# ITG3200_Gyroscope.net
KiCad netlist of a schematic drawn in EAGLE
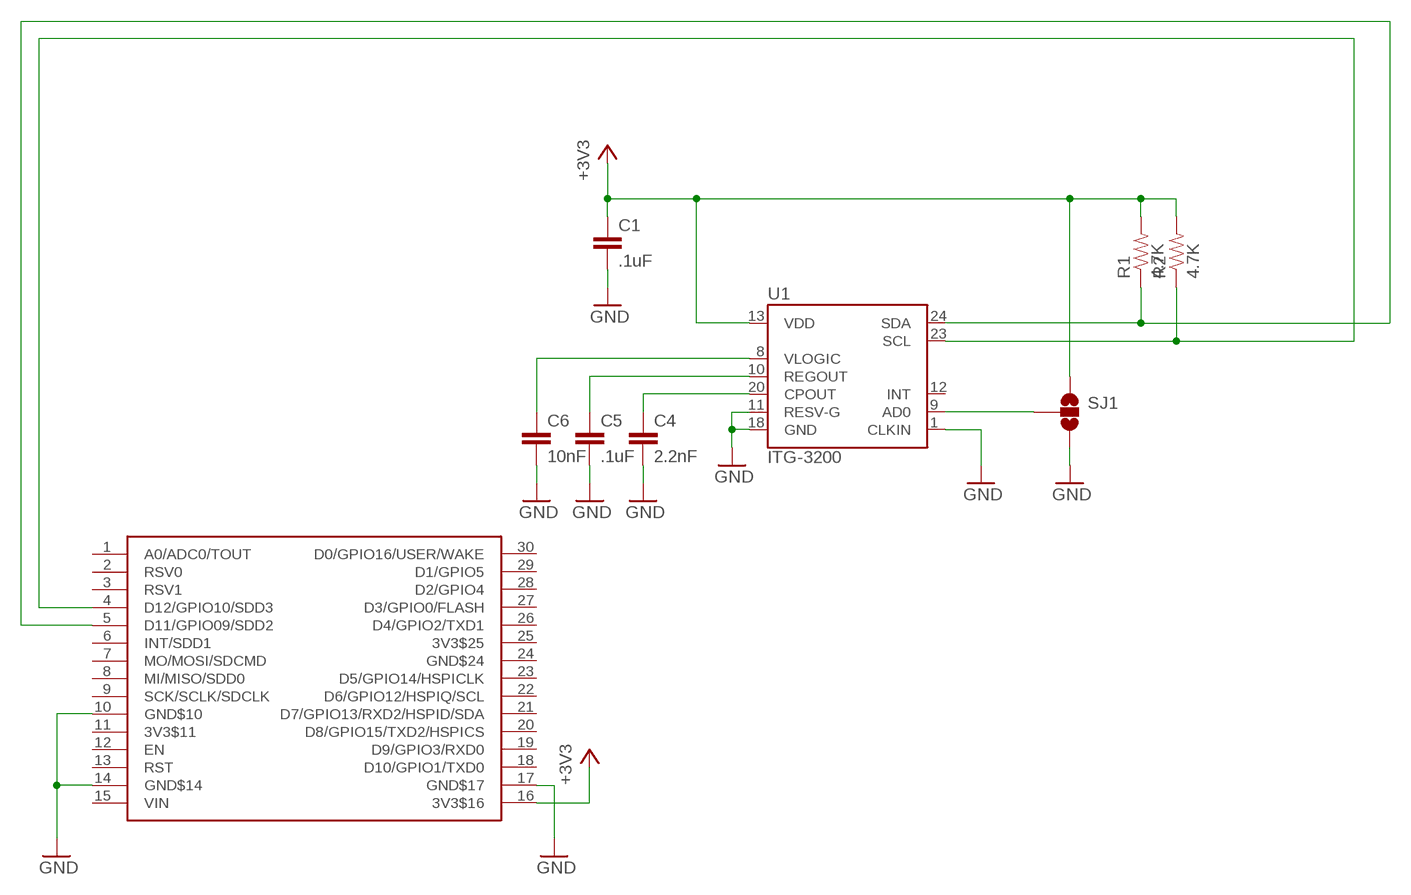
[diagram p0: schematic, sheet 1]

(export (version "E")
  (design (tool "Eeschema 10.0.6"))
  (components
    (comp (ref "C1")
      (value ".1uF")
      (footprint "eagle-import:0603-CAP")
      (libsource (lib "eagle-import") (part "CAP0603-CAP"))
    )
    (comp (ref "C4")
      (value "2.2nF")
      (footprint "eagle-import:0402-CAP")
      (libsource (lib "eagle-import") (part "CAP0402-CAP"))
    )
    (comp (ref "C5")
      (value ".1uF")
      (footprint "eagle-import:0402-CAP")
      (libsource (lib "eagle-import") (part "CAP0402-CAP"))
    )
    (comp (ref "C6")
      (value "10nF")
      (footprint "eagle-import:0402-CAP")
      (libsource (lib "eagle-import") (part "CAP0402-CAP"))
    )
    (comp (ref "R1")
      (value "4.7K")
      (footprint "eagle-import:0402-RES")
      (libsource (lib "eagle-import") (part "RESISTOR0402-RES"))
    )
    (comp (ref "R2")
      (value "4.7K")
      (footprint "eagle-import:0402-RES")
      (libsource (lib "eagle-import") (part "RESISTOR0402-RES"))
    )
    (comp (ref "SJ1")
      (value "SOLDERJUMPER_2WAYT")
      (footprint "eagle-import:SJ_2")
      (libsource (lib "eagle-import") (part "SOLDERJUMPER_2WAYT"))
    )
    (comp (ref "U$2")
      (value "NERDSHIELD")
      (footprint "eagle-import:NERDUINO_STACK")
      (libsource (lib "eagle-import") (part "NERDSHIELD"))
    )
    (comp (ref "U1")
      (value "ITG-3200")
      (footprint "eagle-import:QFN-24")
      (libsource (lib "eagle-import") (part "ITG-3200"))
    )
  )
  (nets
    (net (code "1") (name "+3V3") (class "Default")
      (node (ref "C1") (pin "1") (pinfunction "1_1") (pintype "passive"))
      (node (ref "R1") (pin "2") (pinfunction "2_2") (pintype "passive"))
      (node (ref "R2") (pin "2") (pinfunction "2_2") (pintype "passive"))
      (node (ref "SJ1") (pin "1") (pinfunction "1_1") (pintype "passive"))
      (node (ref "U$2") (pin "16") (pinfunction "3V3$16_16") (pintype "bidirectional"))
      (node (ref "U1") (pin "13") (pinfunction "VDD_13") (pintype "bidirectional"))
    )
    (net (code "2") (name "GND") (class "Default")
      (node (ref "C1") (pin "2") (pinfunction "2_2") (pintype "passive"))
      (node (ref "C4") (pin "2") (pinfunction "2_2") (pintype "passive"))
      (node (ref "C5") (pin "2") (pinfunction "2_2") (pintype "passive"))
      (node (ref "C6") (pin "2") (pinfunction "2_2") (pintype "passive"))
      (node (ref "SJ1") (pin "3") (pinfunction "3_3") (pintype "passive"))
      (node (ref "U$2") (pin "10") (pinfunction "GND$10_10") (pintype "bidirectional"))
      (node (ref "U$2") (pin "14") (pinfunction "GND$14_14") (pintype "bidirectional"))
      (node (ref "U$2") (pin "17") (pinfunction "GND$17_17") (pintype "bidirectional"))
      (node (ref "U1") (pin "1") (pinfunction "CLKIN_1") (pintype "bidirectional"))
      (node (ref "U1") (pin "11") (pinfunction "RESV-G_11") (pintype "bidirectional"))
      (node (ref "U1") (pin "18") (pinfunction "GND_18") (pintype "bidirectional"))
    )
    (net (code "3") (name "Net-(U$2-D11{slash}GPIO09{slash}SDD2)") (class "Default")
      (node (ref "R1") (pin "1") (pinfunction "1_1") (pintype "passive"))
      (node (ref "U$2") (pin "5") (pinfunction "D11/GPIO09/SDD2_5") (pintype "bidirectional"))
      (node (ref "U1") (pin "24") (pinfunction "SDA_24") (pintype "bidirectional"))
    )
    (net (code "4") (name "Net-(U$2-D12{slash}GPIO10{slash}SDD3)") (class "Default")
      (node (ref "R2") (pin "1") (pinfunction "1_1") (pintype "passive"))
      (node (ref "U$2") (pin "4") (pinfunction "D12/GPIO10/SDD3_4") (pintype "bidirectional"))
      (node (ref "U1") (pin "23") (pinfunction "SCL_23") (pintype "bidirectional"))
    )
    (net (code "5") (name "Net-(U1-AD0)") (class "Default")
      (node (ref "SJ1") (pin "2") (pinfunction "2_2") (pintype "passive"))
      (node (ref "U1") (pin "9") (pinfunction "AD0_9") (pintype "bidirectional"))
    )
    (net (code "6") (name "Net-(U1-CPOUT)") (class "Default")
      (node (ref "C4") (pin "1") (pinfunction "1_1") (pintype "passive"))
      (node (ref "U1") (pin "20") (pinfunction "CPOUT_20") (pintype "bidirectional"))
    )
    (net (code "7") (name "Net-(U1-REGOUT)") (class "Default")
      (node (ref "C5") (pin "1") (pinfunction "1_1") (pintype "passive"))
      (node (ref "U1") (pin "10") (pinfunction "REGOUT_10") (pintype "bidirectional"))
    )
    (net (code "8") (name "Net-(U1-VLOGIC)") (class "Default")
      (node (ref "C6") (pin "1") (pinfunction "1_1") (pintype "passive"))
      (node (ref "U1") (pin "8") (pinfunction "VLOGIC_8") (pintype "bidirectional"))
    )
    (net (code "9") (name "unconnected-(U$2-3V3$11-Pad11)") (class "Default")
      (node (ref "U$2") (pin "11") (pinfunction "3V3$11_11") (pintype "bidirectional"))
    )
    (net (code "10") (name "unconnected-(U$2-3V3$25-Pad25)") (class "Default")
      (node (ref "U$2") (pin "25") (pinfunction "3V3$25_25") (pintype "bidirectional"))
    )
    (net (code "11") (name "unconnected-(U$2-A0{slash}ADC0{slash}TOUT-Pad1)") (class "Default")
      (node (ref "U$2") (pin "1") (pinfunction "A0/ADC0/TOUT_1") (pintype "bidirectional"))
    )
    (net (code "12") (name "unconnected-(U$2-D0{slash}GPIO16{slash}USER{slash}WAKE-Pad30)") (class "Default")
      (node (ref "U$2") (pin "30") (pinfunction "D0/GPIO16/USER/WAKE_30") (pintype "bidirectional"))
    )
    (net (code "13") (name "unconnected-(U$2-D1{slash}GPIO5-Pad29)") (class "Default")
      (node (ref "U$2") (pin "29") (pinfunction "D1/GPIO5_29") (pintype "bidirectional"))
    )
    (net (code "14") (name "unconnected-(U$2-D2{slash}GPIO4-Pad28)") (class "Default")
      (node (ref "U$2") (pin "28") (pinfunction "D2/GPIO4_28") (pintype "bidirectional"))
    )
    (net (code "15") (name "unconnected-(U$2-D3{slash}GPIO0{slash}FLASH-Pad27)") (class "Default")
      (node (ref "U$2") (pin "27") (pinfunction "D3/GPIO0/FLASH_27") (pintype "bidirectional"))
    )
    (net (code "16") (name "unconnected-(U$2-D4{slash}GPIO2{slash}TXD1-Pad26)") (class "Default")
      (node (ref "U$2") (pin "26") (pinfunction "D4/GPIO2/TXD1_26") (pintype "bidirectional"))
    )
    (net (code "17") (name "unconnected-(U$2-D5{slash}GPIO14{slash}HSPICLK-Pad23)") (class "Default")
      (node (ref "U$2") (pin "23") (pinfunction "D5/GPIO14/HSPICLK_23") (pintype "bidirectional"))
    )
    (net (code "18") (name "unconnected-(U$2-D6{slash}GPIO12{slash}HSPIQ{slash}SCL-Pad22)") (class "Default")
      (node (ref "U$2") (pin "22") (pinfunction "D6/GPIO12/HSPIQ/SCL_22") (pintype "bidirectional"))
    )
    (net (code "19") (name "unconnected-(U$2-D7{slash}GPIO13{slash}RXD2{slash}HSPID{slash}SDA-Pad21)") (class "Default")
      (node (ref "U$2") (pin "21") (pinfunction "D7/GPIO13/RXD2/HSPID/SDA_21") (pintype "bidirectional"))
    )
    (net (code "20") (name "unconnected-(U$2-D8{slash}GPIO15{slash}TXD2{slash}HSPICS-Pad20)") (class "Default")
      (node (ref "U$2") (pin "20") (pinfunction "D8/GPIO15/TXD2/HSPICS_20") (pintype "bidirectional"))
    )
    (net (code "21") (name "unconnected-(U$2-D9{slash}GPIO3{slash}RXD0-Pad19)") (class "Default")
      (node (ref "U$2") (pin "19") (pinfunction "D9/GPIO3/RXD0_19") (pintype "bidirectional"))
    )
    (net (code "22") (name "unconnected-(U$2-D10{slash}GPIO1{slash}TXD0-Pad18)") (class "Default")
      (node (ref "U$2") (pin "18") (pinfunction "D10/GPIO1/TXD0_18") (pintype "bidirectional"))
    )
    (net (code "23") (name "unconnected-(U$2-EN-Pad12)") (class "Default")
      (node (ref "U$2") (pin "12") (pinfunction "EN_12") (pintype "bidirectional"))
    )
    (net (code "24") (name "unconnected-(U$2-GND$24-Pad24)") (class "Default")
      (node (ref "U$2") (pin "24") (pinfunction "GND$24_24") (pintype "bidirectional"))
    )
    (net (code "25") (name "unconnected-(U$2-INT{slash}SDD1-Pad6)") (class "Default")
      (node (ref "U$2") (pin "6") (pinfunction "INT/SDD1_6") (pintype "bidirectional"))
    )
    (net (code "26") (name "unconnected-(U$2-MI{slash}MISO{slash}SDD0-Pad8)") (class "Default")
      (node (ref "U$2") (pin "8") (pinfunction "MI/MISO/SDD0_8") (pintype "bidirectional"))
    )
    (net (code "27") (name "unconnected-(U$2-MO{slash}MOSI{slash}SDCMD-Pad7)") (class "Default")
      (node (ref "U$2") (pin "7") (pinfunction "MO/MOSI/SDCMD_7") (pintype "bidirectional"))
    )
    (net (code "28") (name "unconnected-(U$2-RST-Pad13)") (class "Default")
      (node (ref "U$2") (pin "13") (pinfunction "RST_13") (pintype "bidirectional"))
    )
    (net (code "29") (name "unconnected-(U$2-RSV0-Pad2)") (class "Default")
      (node (ref "U$2") (pin "2") (pinfunction "RSV0_2") (pintype "bidirectional"))
    )
    (net (code "30") (name "unconnected-(U$2-RSV1-Pad3)") (class "Default")
      (node (ref "U$2") (pin "3") (pinfunction "RSV1_3") (pintype "bidirectional"))
    )
    (net (code "31") (name "unconnected-(U$2-SCK{slash}SCLK{slash}SDCLK-Pad9)") (class "Default")
      (node (ref "U$2") (pin "9") (pinfunction "SCK/SCLK/SDCLK_9") (pintype "bidirectional"))
    )
    (net (code "32") (name "unconnected-(U$2-VIN-Pad15)") (class "Default")
      (node (ref "U$2") (pin "15") (pinfunction "VIN_15") (pintype "bidirectional"))
    )
    (net (code "33") (name "unconnected-(U1-INT-Pad12)") (class "Default")
      (node (ref "U1") (pin "12") (pinfunction "INT_12") (pintype "bidirectional"))
    )
  )
)
